# usbTerminal.net
KiCad netlist of a schematic drawn in EAGLE
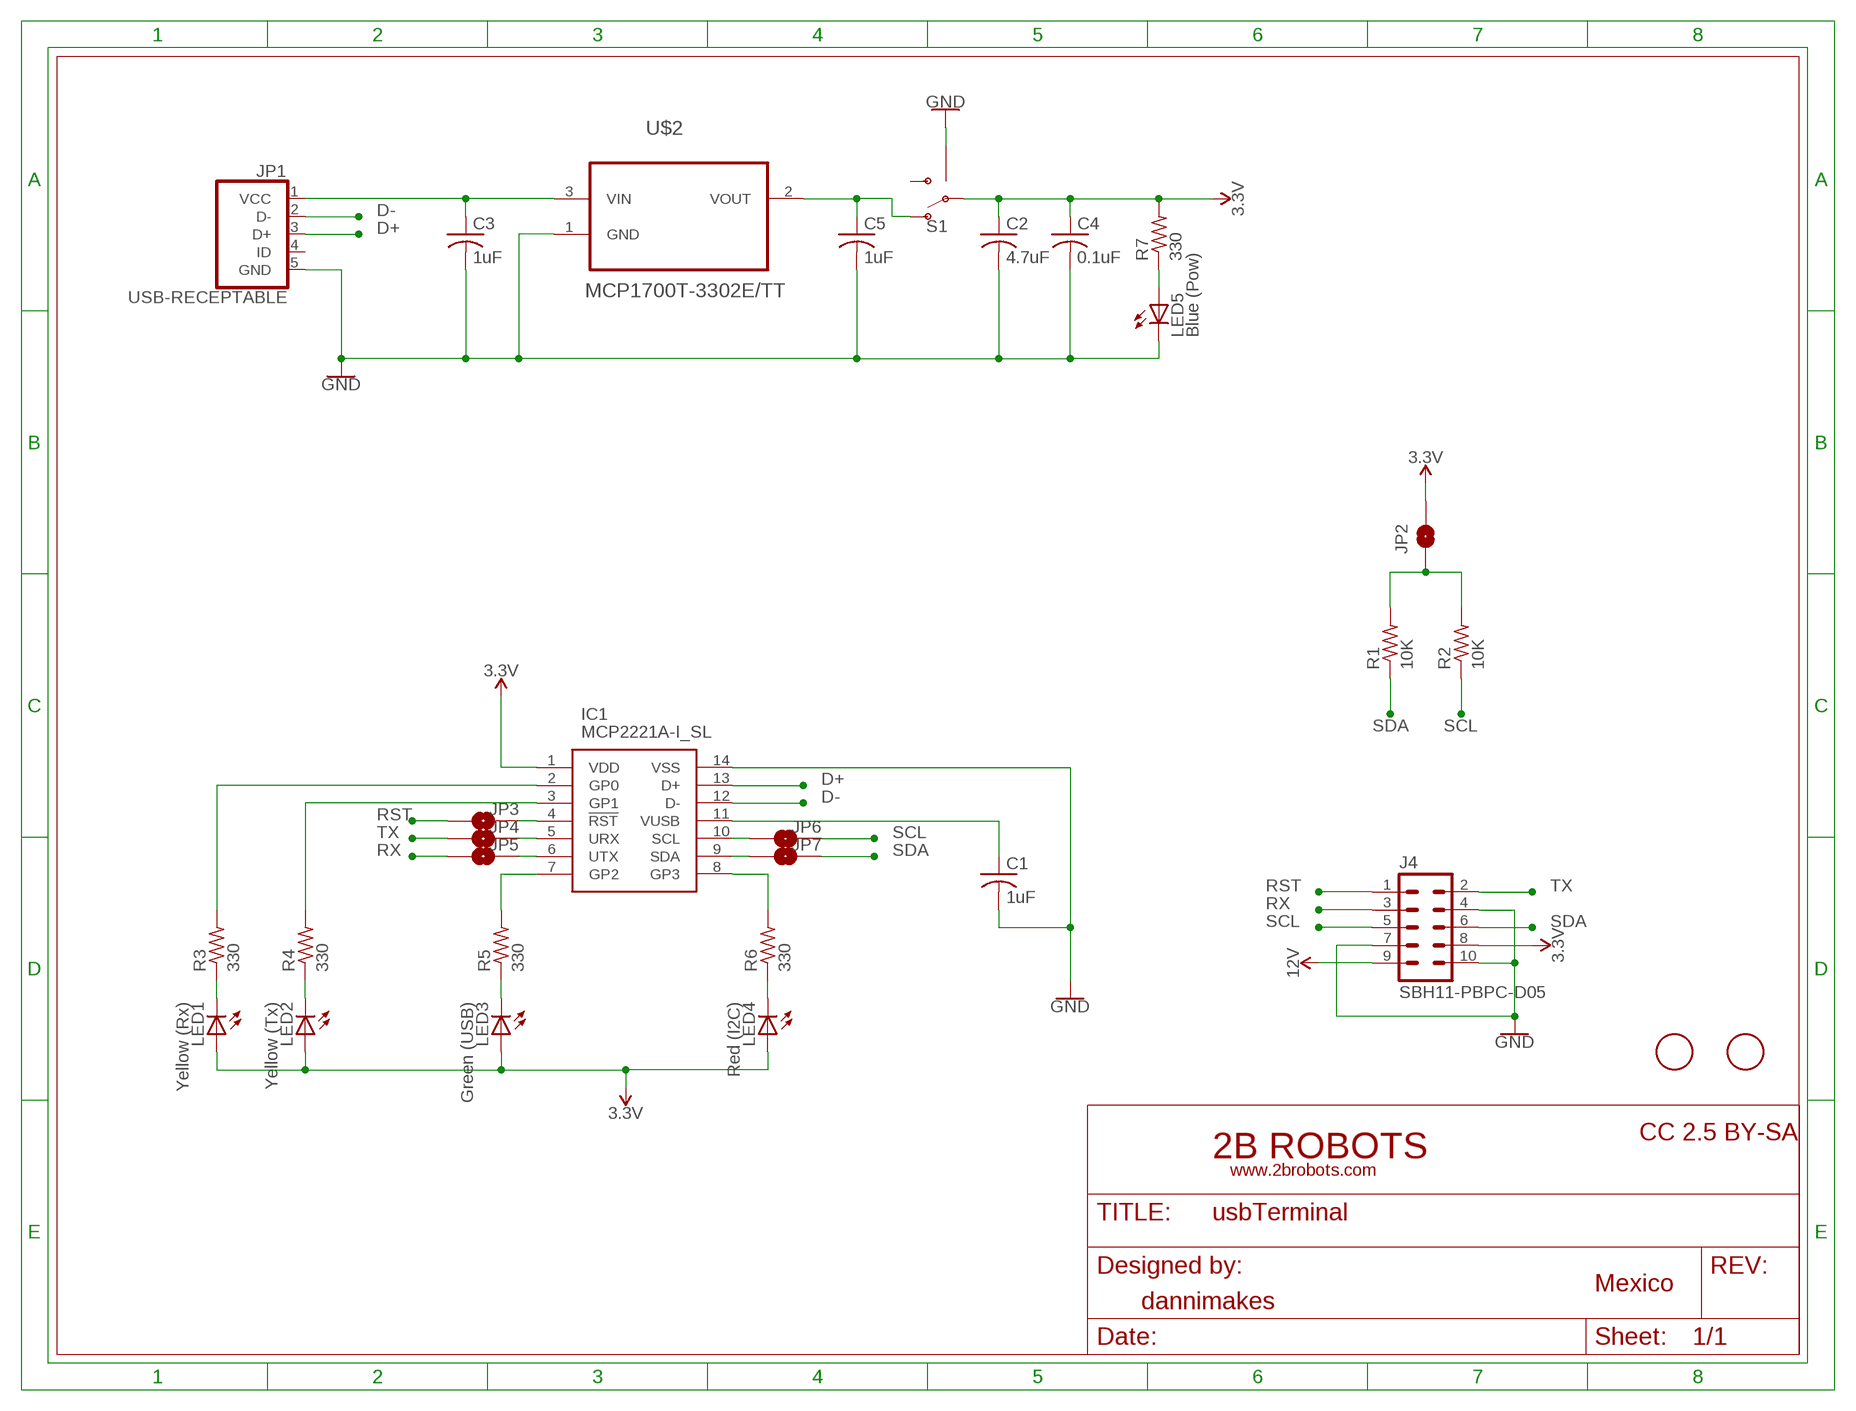
[diagram p0: schematic, sheet 1]

(export (version "E")
  (design (tool "Eeschema 10.0.6"))
  (components
    (comp (ref "C1")
      (value "1uF")
      (footprint "eagle-import:C0603K")
      (libsource (lib "eagle-import") (part "C-USC0603K"))
    )
    (comp (ref "C2")
      (value "4.7uF")
      (footprint "eagle-import:C0805K")
      (libsource (lib "eagle-import") (part "C-USC0805K"))
    )
    (comp (ref "C3")
      (value "1uF")
      (footprint "eagle-import:C0603K")
      (libsource (lib "eagle-import") (part "C-USC0603K"))
    )
    (comp (ref "C4")
      (value "0.1uF")
      (footprint "eagle-import:C0603K")
      (libsource (lib "eagle-import") (part "C-USC0603K"))
    )
    (comp (ref "C5")
      (value "1uF")
      (footprint "eagle-import:C0603K")
      (libsource (lib "eagle-import") (part "C-USC0603K"))
    )
    (comp (ref "IC1")
      (value "MCP2221A-I_SL")
      (footprint "eagle-import:SOIC127P600X175-14N")
      (fields
        (field (name "MANUFACTURER_PART_NUMBER") "MCP2221A-I/SL")
        (field (name "MOUSER_PART_NUMBER") "579-MCP2221A-I/SL")
      )
      (libsource (lib "eagle-import") (part "MCP2221A-I_SL"))
    )
    (comp (ref "J4")
      (value "SBH11-PBPC-D05")
      (footprint "eagle-import:SBH11-PBPC-D05")
      (libsource (lib "eagle-import") (part "SBH11-PBPC-D05"))
    )
    (comp (ref "JP1")
      (value "USB-RECEPTABLE")
      (footprint "eagle-import:FCI-10103594-0001LF")
      (libsource (lib "eagle-import") (part "USB-RECEPTABLE"))
    )
    (comp (ref "JP2")
      (value "JUMPER-SMT_2_NO_SILK")
      (footprint "eagle-import:SMT-JUMPER_2_NO_SILK")
      (libsource (lib "eagle-import") (part "JUMPER-SMT_2_NO_SILK"))
    )
    (comp (ref "JP3")
      (value "JUMPER-SMT_2_NO_SILK")
      (footprint "eagle-import:SMT-JUMPER_2_NO_SILK")
      (libsource (lib "eagle-import") (part "JUMPER-SMT_2_NO_SILK"))
    )
    (comp (ref "JP4")
      (value "JUMPER-SMT_2_NO_SILK")
      (footprint "eagle-import:SMT-JUMPER_2_NO_SILK")
      (libsource (lib "eagle-import") (part "JUMPER-SMT_2_NO_SILK"))
    )
    (comp (ref "JP5")
      (value "JUMPER-SMT_2_NO_SILK")
      (footprint "eagle-import:SMT-JUMPER_2_NO_SILK")
      (libsource (lib "eagle-import") (part "JUMPER-SMT_2_NO_SILK"))
    )
    (comp (ref "JP6")
      (value "JUMPER-SMT_2_NO_SILK")
      (footprint "eagle-import:SMT-JUMPER_2_NO_SILK")
      (libsource (lib "eagle-import") (part "JUMPER-SMT_2_NO_SILK"))
    )
    (comp (ref "JP7")
      (value "JUMPER-SMT_2_NO_SILK")
      (footprint "eagle-import:SMT-JUMPER_2_NO_SILK")
      (libsource (lib "eagle-import") (part "JUMPER-SMT_2_NO_SILK"))
    )
    (comp (ref "LED1")
      (value "Yellow (Rx)")
      (footprint "eagle-import:CHIPLED_1206")
      (libsource (lib "eagle-import") (part "LEDCHIPLED_1206"))
    )
    (comp (ref "LED2")
      (value "Yellow (Tx)")
      (footprint "eagle-import:CHIPLED_1206")
      (libsource (lib "eagle-import") (part "LEDCHIPLED_1206"))
    )
    (comp (ref "LED3")
      (value "Green (USB)")
      (footprint "eagle-import:CHIPLED_1206")
      (libsource (lib "eagle-import") (part "LEDCHIPLED_1206"))
    )
    (comp (ref "LED4")
      (value "Red (I2C)")
      (footprint "eagle-import:CHIPLED_1206")
      (libsource (lib "eagle-import") (part "LEDCHIPLED_1206"))
    )
    (comp (ref "LED5")
      (value "Blue (Pow)")
      (footprint "eagle-import:CHIPLED_1206")
      (libsource (lib "eagle-import") (part "LEDCHIPLED_1206"))
    )
    (comp (ref "R1")
      (value "10K")
      (footprint "eagle-import:R0805")
      (libsource (lib "eagle-import") (part "R-US_R0805"))
    )
    (comp (ref "R2")
      (value "10K")
      (footprint "eagle-import:R0805")
      (libsource (lib "eagle-import") (part "R-US_R0805"))
    )
    (comp (ref "R3")
      (value "330")
      (footprint "eagle-import:R0805")
      (libsource (lib "eagle-import") (part "R-US_R0805"))
    )
    (comp (ref "R4")
      (value "330")
      (footprint "eagle-import:R0805")
      (libsource (lib "eagle-import") (part "R-US_R0805"))
    )
    (comp (ref "R5")
      (value "330")
      (footprint "eagle-import:R0805")
      (libsource (lib "eagle-import") (part "R-US_R0805"))
    )
    (comp (ref "R6")
      (value "330")
      (footprint "eagle-import:R0805")
      (libsource (lib "eagle-import") (part "R-US_R0805"))
    )
    (comp (ref "R7")
      (value "330")
      (footprint "eagle-import:R0805")
      (libsource (lib "eagle-import") (part "R-US_R0805"))
    )
    (comp (ref "S1")
      (value "SWITCH-SPDT-SMD-RIGHT-ANGLE")
      (footprint "eagle-import:SWITCH_SPST_SMD_A")
      (libsource (lib "eagle-import") (part "SWITCH-SPDT-SMD-RIGHT-ANGLE"))
    )
    (comp (ref "U$1")
      (value "FIDUCIAL")
      (footprint "eagle-import:FIDUCIAL_1MM")
      (libsource (lib "eagle-import") (part "FIDUCIAL"))
    )
    (comp (ref "U$2")
      (value "MCP1700T-3302E/TT")
      (footprint "eagle-import:SOT95P237X112-3N")
      (libsource (lib "eagle-import") (part "MCP1700T-3302E/TT"))
    )
    (comp (ref "U$3")
      (value "FIDUCIAL")
      (footprint "eagle-import:FIDUCIAL_1MM")
      (libsource (lib "eagle-import") (part "FIDUCIAL"))
    )
  )
  (nets
    (net (code "1") (name "/D+") (class "Default")
      (node (ref "IC1") (pin "13") (pinfunction "D+_13") (pintype "bidirectional"))
      (node (ref "JP1") (pin "3") (pinfunction "D+_3") (pintype "bidirectional"))
    )
    (net (code "2") (name "/D-") (class "Default")
      (node (ref "IC1") (pin "12") (pinfunction "D-_12") (pintype "bidirectional"))
      (node (ref "JP1") (pin "2") (pinfunction "D-_2") (pintype "bidirectional"))
    )
    (net (code "3") (name "/RST") (class "Default")
      (node (ref "J4") (pin "1") (pinfunction "1_1") (pintype "passive"))
      (node (ref "JP3") (pin "2") (pinfunction "2_2") (pintype "passive"))
    )
    (net (code "4") (name "/RX") (class "Default")
      (node (ref "J4") (pin "3") (pinfunction "3_3") (pintype "passive"))
      (node (ref "JP5") (pin "2") (pinfunction "2_2") (pintype "passive"))
    )
    (net (code "5") (name "/SCL") (class "Default")
      (node (ref "J4") (pin "5") (pinfunction "5_5") (pintype "passive"))
      (node (ref "JP6") (pin "1") (pinfunction "1_1") (pintype "passive"))
      (node (ref "R2") (pin "1") (pinfunction "1_1") (pintype "passive"))
    )
    (net (code "6") (name "/SDA") (class "Default")
      (node (ref "J4") (pin "6") (pinfunction "6_6") (pintype "passive"))
      (node (ref "JP7") (pin "1") (pinfunction "1_1") (pintype "passive"))
      (node (ref "R1") (pin "1") (pinfunction "1_1") (pintype "passive"))
    )
    (net (code "7") (name "/TX") (class "Default")
      (node (ref "J4") (pin "2") (pinfunction "2_2") (pintype "passive"))
      (node (ref "JP4") (pin "2") (pinfunction "2_2") (pintype "passive"))
    )
    (net (code "8") (name "3.3V") (class "Default")
      (node (ref "C2") (pin "1") (pinfunction "1_1") (pintype "passive"))
      (node (ref "C4") (pin "1") (pinfunction "1_1") (pintype "passive"))
      (node (ref "IC1") (pin "1") (pinfunction "VDD_1") (pintype "bidirectional"))
      (node (ref "J4") (pin "8") (pinfunction "8_8") (pintype "passive"))
      (node (ref "JP2") (pin "2") (pinfunction "2_2") (pintype "passive"))
      (node (ref "LED1") (pin "A") (pinfunction "A_A") (pintype "passive"))
      (node (ref "LED2") (pin "A") (pinfunction "A_A") (pintype "passive"))
      (node (ref "LED3") (pin "A") (pinfunction "A_A") (pintype "passive"))
      (node (ref "LED4") (pin "A") (pinfunction "A_A") (pintype "passive"))
      (node (ref "R7") (pin "2") (pinfunction "2_2") (pintype "passive"))
      (node (ref "S1") (pin "2") (pinfunction "P_2") (pintype "passive"))
    )
    (net (code "9") (name "12V") (class "Default")
      (node (ref "J4") (pin "9") (pinfunction "9_9") (pintype "passive"))
    )
    (net (code "10") (name "GND") (class "Default")
      (node (ref "C1") (pin "2") (pinfunction "2_2") (pintype "passive"))
      (node (ref "C2") (pin "2") (pinfunction "2_2") (pintype "passive"))
      (node (ref "C3") (pin "2") (pinfunction "2_2") (pintype "passive"))
      (node (ref "C4") (pin "2") (pinfunction "2_2") (pintype "passive"))
      (node (ref "C5") (pin "2") (pinfunction "2_2") (pintype "passive"))
      (node (ref "IC1") (pin "14") (pinfunction "VSS_14") (pintype "bidirectional"))
      (node (ref "J4") (pin "10") (pinfunction "10_10") (pintype "passive"))
      (node (ref "J4") (pin "4") (pinfunction "4_4") (pintype "passive"))
      (node (ref "J4") (pin "7") (pinfunction "7_7") (pintype "passive"))
      (node (ref "JP1") (pin "5") (pinfunction "GND_5") (pintype "bidirectional"))
      (node (ref "LED5") (pin "C") (pinfunction "C_C") (pintype "passive"))
      (node (ref "S1") (pin "GND1") (pinfunction "GND_GND1") (pintype "bidirectional"))
      (node (ref "S1") (pin "GND2") (pinfunction "GND_GND2") (pintype "bidirectional"))
      (node (ref "S1") (pin "GND3") (pinfunction "GND_GND3") (pintype "bidirectional"))
      (node (ref "S1") (pin "GND4") (pinfunction "GND_GND4") (pintype "bidirectional"))
      (node (ref "U$2") (pin "1") (pinfunction "GND_1") (pintype "passive"))
    )
    (net (code "11") (name "Net-(IC1-GP0)") (class "Default")
      (node (ref "IC1") (pin "2") (pinfunction "GP0_2") (pintype "bidirectional"))
      (node (ref "R3") (pin "2") (pinfunction "2_2") (pintype "passive"))
    )
    (net (code "12") (name "Net-(IC1-GP1)") (class "Default")
      (node (ref "IC1") (pin "3") (pinfunction "GP1_3") (pintype "bidirectional"))
      (node (ref "R4") (pin "2") (pinfunction "2_2") (pintype "passive"))
    )
    (net (code "13") (name "Net-(IC1-GP2)") (class "Default")
      (node (ref "IC1") (pin "7") (pinfunction "GP2_7") (pintype "bidirectional"))
      (node (ref "R5") (pin "2") (pinfunction "2_2") (pintype "passive"))
    )
    (net (code "14") (name "Net-(IC1-GP3)") (class "Default")
      (node (ref "IC1") (pin "8") (pinfunction "GP3_8") (pintype "bidirectional"))
      (node (ref "R6") (pin "2") (pinfunction "2_2") (pintype "passive"))
    )
    (net (code "15") (name "Net-(IC1-SCL)") (class "Default")
      (node (ref "IC1") (pin "10") (pinfunction "SCL_10") (pintype "bidirectional"))
      (node (ref "JP6") (pin "2") (pinfunction "2_2") (pintype "passive"))
    )
    (net (code "16") (name "Net-(IC1-SDA)") (class "Default")
      (node (ref "IC1") (pin "9") (pinfunction "SDA_9") (pintype "bidirectional"))
      (node (ref "JP7") (pin "2") (pinfunction "2_2") (pintype "passive"))
    )
    (net (code "17") (name "Net-(IC1-URX)") (class "Default")
      (node (ref "IC1") (pin "5") (pinfunction "URX_5") (pintype "bidirectional"))
      (node (ref "JP4") (pin "1") (pinfunction "1_1") (pintype "passive"))
    )
    (net (code "18") (name "Net-(IC1-UTX)") (class "Default")
      (node (ref "IC1") (pin "6") (pinfunction "UTX_6") (pintype "bidirectional"))
      (node (ref "JP5") (pin "1") (pinfunction "1_1") (pintype "passive"))
    )
    (net (code "19") (name "Net-(IC1-VUSB)") (class "Default")
      (node (ref "C1") (pin "1") (pinfunction "1_1") (pintype "passive"))
      (node (ref "IC1") (pin "11") (pinfunction "VUSB_11") (pintype "bidirectional"))
    )
    (net (code "20") (name "Net-(IC1-~{RST})") (class "Default")
      (node (ref "IC1") (pin "4") (pinfunction "~{RST}_4") (pintype "bidirectional"))
      (node (ref "JP3") (pin "1") (pinfunction "1_1") (pintype "passive"))
    )
    (net (code "21") (name "Net-(JP1-VCC)") (class "Default")
      (node (ref "C3") (pin "1") (pinfunction "1_1") (pintype "passive"))
      (node (ref "JP1") (pin "1") (pinfunction "VCC_1") (pintype "bidirectional"))
      (node (ref "U$2") (pin "3") (pinfunction "VIN_3") (pintype "input"))
    )
    (net (code "22") (name "Net-(JP2-Pad1)") (class "Default")
      (node (ref "JP2") (pin "1") (pinfunction "1_1") (pintype "passive"))
      (node (ref "R1") (pin "2") (pinfunction "2_2") (pintype "passive"))
      (node (ref "R2") (pin "2") (pinfunction "2_2") (pintype "passive"))
    )
    (net (code "23") (name "Net-(LED1-PadC)") (class "Default")
      (node (ref "LED1") (pin "C") (pinfunction "C_C") (pintype "passive"))
      (node (ref "R3") (pin "1") (pinfunction "1_1") (pintype "passive"))
    )
    (net (code "24") (name "Net-(LED2-PadC)") (class "Default")
      (node (ref "LED2") (pin "C") (pinfunction "C_C") (pintype "passive"))
      (node (ref "R4") (pin "1") (pinfunction "1_1") (pintype "passive"))
    )
    (net (code "25") (name "Net-(LED3-PadC)") (class "Default")
      (node (ref "LED3") (pin "C") (pinfunction "C_C") (pintype "passive"))
      (node (ref "R5") (pin "1") (pinfunction "1_1") (pintype "passive"))
    )
    (net (code "26") (name "Net-(LED4-PadC)") (class "Default")
      (node (ref "LED4") (pin "C") (pinfunction "C_C") (pintype "passive"))
      (node (ref "R6") (pin "1") (pinfunction "1_1") (pintype "passive"))
    )
    (net (code "27") (name "Net-(LED5-PadA)") (class "Default")
      (node (ref "LED5") (pin "A") (pinfunction "A_A") (pintype "passive"))
      (node (ref "R7") (pin "1") (pinfunction "1_1") (pintype "passive"))
    )
    (net (code "28") (name "Net-(S1-O)") (class "Default")
      (node (ref "C5") (pin "1") (pinfunction "1_1") (pintype "passive"))
      (node (ref "S1") (pin "1") (pinfunction "O_1") (pintype "passive"))
      (node (ref "U$2") (pin "2") (pinfunction "VOUT_2") (pintype "output"))
    )
    (net (code "29") (name "unconnected-(JP1-ID-Pad4)") (class "Default")
      (node (ref "JP1") (pin "4") (pinfunction "ID_4") (pintype "bidirectional"))
    )
    (net (code "30") (name "unconnected-(S1-S-Pad3)") (class "Default")
      (node (ref "S1") (pin "3") (pinfunction "S_3") (pintype "passive"))
    )
  )
)
